# CAN_TERM_LEFT.net
KiCad netlist of a schematic drawn in Altium Designer
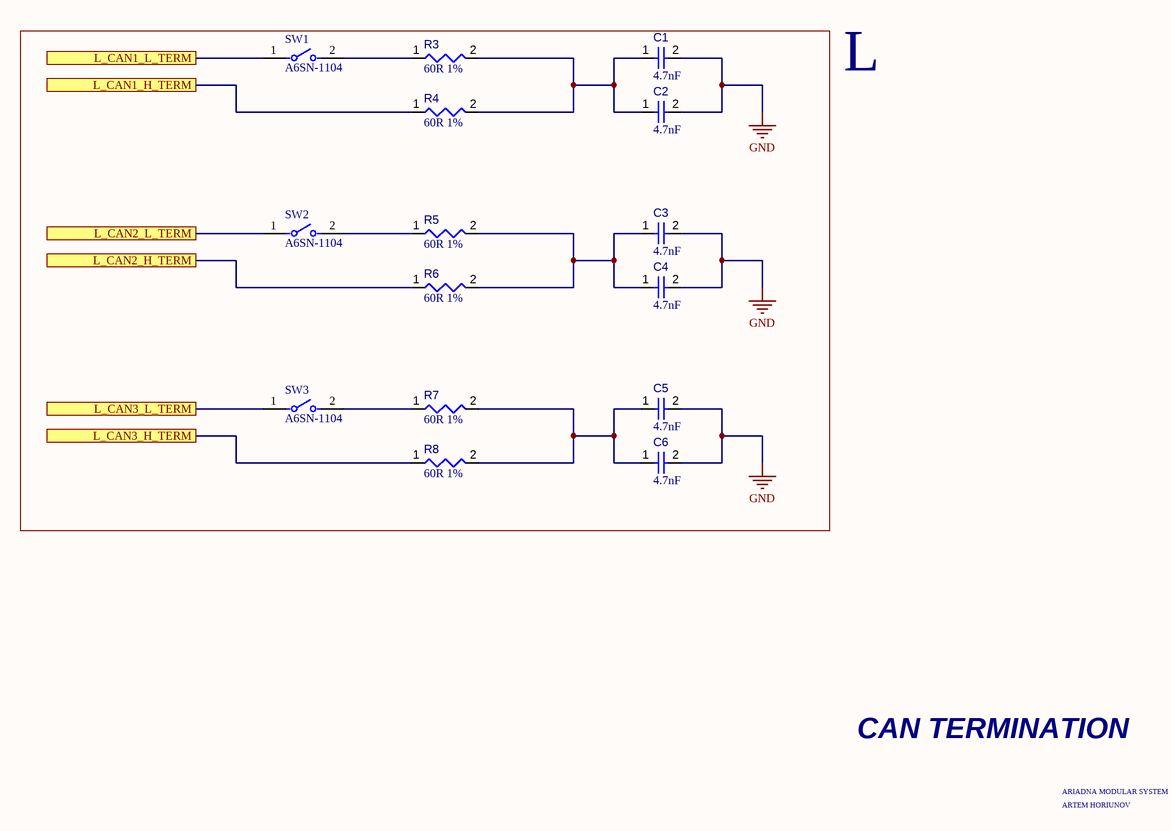
[diagram p0: CAN_TERM_LEFT.SchDoc]

(export (version "E")
  (design (tool "Eeschema 10.0.6"))
  (components
    (comp (ref "C1")
      (value "4.7nF")
      (footprint "CAPC0805(2012)145_L")
      (description "Chip Capacitor, 4.7µF +/-40%, 25V, 0805, Thickness 1.45 mm")
      (fields (field (name "TOLERANCE") "20%") (field (name "Comment") "Capacitor 4.7µF +/-40% 25V 0805"))
      (libsource (lib "WUST") (part "CAP-NP-2"))
    )
    (comp (ref "C2")
      (value "4.7nF")
      (footprint "CAPC0805(2012)145_L")
      (description "Chip Capacitor, 4.7µF +/-40%, 25V, 0805, Thickness 1.45 mm")
      (fields (field (name "TOLERANCE") "20%") (field (name "Comment") "Capacitor 4.7µF +/-40% 25V 0805"))
      (libsource (lib "WUST") (part "CAP-NP-2"))
    )
    (comp (ref "C3")
      (value "4.7nF")
      (footprint "CAPC0805(2012)145_L")
      (description "Chip Capacitor, 4.7µF +/-40%, 25V, 0805, Thickness 1.45 mm")
      (fields (field (name "TOLERANCE") "20%") (field (name "Comment") "Capacitor 4.7µF +/-40% 25V 0805"))
      (libsource (lib "WUST") (part "CAP-NP-2"))
    )
    (comp (ref "C4")
      (value "4.7nF")
      (footprint "CAPC0805(2012)145_L")
      (description "Chip Capacitor, 4.7µF +/-40%, 25V, 0805, Thickness 1.45 mm")
      (fields (field (name "TOLERANCE") "20%") (field (name "Comment") "Capacitor 4.7µF +/-40% 25V 0805"))
      (libsource (lib "WUST") (part "CAP-NP-2"))
    )
    (comp (ref "C5")
      (value "4.7nF")
      (footprint "CAPC0805(2012)145_L")
      (description "Chip Capacitor, 4.7µF +/-40%, 25V, 0805, Thickness 1.45 mm")
      (fields (field (name "TOLERANCE") "20%") (field (name "Comment") "Capacitor 4.7µF +/-40% 25V 0805"))
      (libsource (lib "WUST") (part "CAP-NP-2"))
    )
    (comp (ref "C6")
      (value "4.7nF")
      (footprint "CAPC0805(2012)145_L")
      (description "Chip Capacitor, 4.7µF +/-40%, 25V, 0805, Thickness 1.45 mm")
      (fields (field (name "TOLERANCE") "20%") (field (name "Comment") "Capacitor 4.7µF +/-40% 25V 0805"))
      (libsource (lib "WUST") (part "CAP-NP-2"))
    )
    (comp (ref "R3")
      (value "60R 1%")
      (footprint "RESC0805(2012)_L")
      (description "4R7 0.125W 5% 0805 (2012 Metric)  SMD")
      (fields (field (name "POWER") "125mW") (field (name "TOLERANCE") "5%"))
      (libsource (lib "WUST") (part "4D7R5J"))
    )
    (comp (ref "R4")
      (value "60R 1%")
      (footprint "RESC0805(2012)_L")
      (description "4R7 0.125W 5% 0805 (2012 Metric)  SMD")
      (fields (field (name "POWER") "125mW") (field (name "TOLERANCE") "5%"))
      (libsource (lib "WUST") (part "4D7R5J"))
    )
    (comp (ref "R5")
      (value "60R 1%")
      (footprint "RESC0805(2012)_L")
      (description "4R7 0.125W 5% 0805 (2012 Metric)  SMD")
      (fields (field (name "POWER") "125mW") (field (name "TOLERANCE") "5%"))
      (libsource (lib "WUST") (part "4D7R5J"))
    )
    (comp (ref "R6")
      (value "60R 1%")
      (footprint "RESC0805(2012)_L")
      (description "4R7 0.125W 5% 0805 (2012 Metric)  SMD")
      (fields (field (name "POWER") "125mW") (field (name "TOLERANCE") "5%"))
      (libsource (lib "WUST") (part "4D7R5J"))
    )
    (comp (ref "R7")
      (value "60R 1%")
      (footprint "RESC0805(2012)_L")
      (description "4R7 0.125W 5% 0805 (2012 Metric)  SMD")
      (fields (field (name "POWER") "125mW") (field (name "TOLERANCE") "5%"))
      (libsource (lib "WUST") (part "4D7R5J"))
    )
    (comp (ref "R8")
      (value "60R 1%")
      (footprint "RESC0805(2012)_L")
      (description "4R7 0.125W 5% 0805 (2012 Metric)  SMD")
      (fields (field (name "POWER") "125mW") (field (name "TOLERANCE") "5%"))
      (libsource (lib "WUST") (part "4D7R5J"))
    )
    (comp (ref "SW1")
      (value "A6SN-1104")
      (footprint "FP-A6SN-1104-MFG")
      (description "SWITCH SLIDE DIP SPST 25MA 24V")
      (libsource (lib "Altium Content Vault") (part "bb27bde45df87f1f469753f287ef5ae"))
    )
    (comp (ref "SW2")
      (value "A6SN-1104")
      (footprint "FP-A6SN-1104-MFG")
      (description "SWITCH SLIDE DIP SPST 25MA 24V")
      (libsource (lib "Altium Content Vault") (part "bb27bde45df87f1f469753f287ef5ae"))
    )
    (comp (ref "SW3")
      (value "A6SN-1104")
      (footprint "FP-A6SN-1104-MFG")
      (description "SWITCH SLIDE DIP SPST 25MA 24V")
      (libsource (lib "Altium Content Vault") (part "bb27bde45df87f1f469753f287ef5ae"))
    )
  )
  (nets
    (net (code "1") (name "/L_CAN1_H_TERM") (class "Default")
      (node (ref "R4") (pin "1") (pinfunction "1_1") (pintype "passive"))
    )
    (net (code "2") (name "/L_CAN1_L_TERM") (class "Default")
      (node (ref "SW1") (pin "1") (pinfunction "1_1") (pintype "passive"))
    )
    (net (code "3") (name "/L_CAN2_H_TERM") (class "Default")
      (node (ref "R6") (pin "1") (pinfunction "1_1") (pintype "passive"))
    )
    (net (code "4") (name "/L_CAN2_L_TERM") (class "Default")
      (node (ref "SW2") (pin "1") (pinfunction "1_1") (pintype "passive"))
    )
    (net (code "5") (name "/L_CAN3_H_TERM") (class "Default")
      (node (ref "R8") (pin "1") (pinfunction "1_1") (pintype "passive"))
    )
    (net (code "6") (name "/L_CAN3_L_TERM") (class "Default")
      (node (ref "SW3") (pin "1") (pinfunction "1_1") (pintype "passive"))
    )
    (net (code "7") (name "GND") (class "Default")
      (node (ref "C1") (pin "2") (pinfunction "2_2") (pintype "passive"))
      (node (ref "C2") (pin "2") (pinfunction "2_2") (pintype "passive"))
      (node (ref "C3") (pin "2") (pinfunction "2_2") (pintype "passive"))
      (node (ref "C4") (pin "2") (pinfunction "2_2") (pintype "passive"))
      (node (ref "C5") (pin "2") (pinfunction "2_2") (pintype "passive"))
      (node (ref "C6") (pin "2") (pinfunction "2_2") (pintype "passive"))
    )
    (net (code "8") (name "Net-(C1-Pad1)") (class "Default")
      (node (ref "C1") (pin "1") (pinfunction "1_1") (pintype "passive"))
      (node (ref "C2") (pin "1") (pinfunction "1_1") (pintype "passive"))
      (node (ref "R3") (pin "2") (pinfunction "2_2") (pintype "passive"))
      (node (ref "R4") (pin "2") (pinfunction "2_2") (pintype "passive"))
    )
    (net (code "9") (name "Net-(C3-Pad1)") (class "Default")
      (node (ref "C3") (pin "1") (pinfunction "1_1") (pintype "passive"))
      (node (ref "C4") (pin "1") (pinfunction "1_1") (pintype "passive"))
      (node (ref "R5") (pin "2") (pinfunction "2_2") (pintype "passive"))
      (node (ref "R6") (pin "2") (pinfunction "2_2") (pintype "passive"))
    )
    (net (code "10") (name "Net-(C5-Pad1)") (class "Default")
      (node (ref "C5") (pin "1") (pinfunction "1_1") (pintype "passive"))
      (node (ref "C6") (pin "1") (pinfunction "1_1") (pintype "passive"))
      (node (ref "R7") (pin "2") (pinfunction "2_2") (pintype "passive"))
      (node (ref "R8") (pin "2") (pinfunction "2_2") (pintype "passive"))
    )
    (net (code "11") (name "Net-(R3-Pad1)") (class "Default")
      (node (ref "R3") (pin "1") (pinfunction "1_1") (pintype "passive"))
      (node (ref "SW1") (pin "2") (pinfunction "2_2") (pintype "passive"))
    )
    (net (code "12") (name "Net-(R5-Pad1)") (class "Default")
      (node (ref "R5") (pin "1") (pinfunction "1_1") (pintype "passive"))
      (node (ref "SW2") (pin "2") (pinfunction "2_2") (pintype "passive"))
    )
    (net (code "13") (name "Net-(R7-Pad1)") (class "Default")
      (node (ref "R7") (pin "1") (pinfunction "1_1") (pintype "passive"))
      (node (ref "SW3") (pin "2") (pinfunction "2_2") (pintype "passive"))
    )
  )
)
